# BMS_Sense_Board.net
KiCad netlist of a schematic drawn in Altium Designer
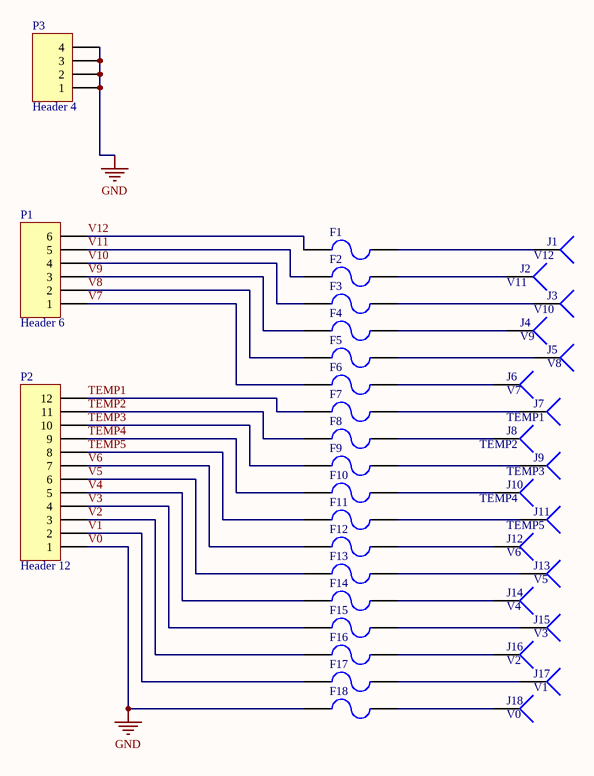
[diagram p0: BMS Sense Board.SchDoc]

(export (version "E")
  (design (tool "Eeschema 10.0.6"))
  (components
    (comp (ref "F1")
      (value "Fuse 2")
      (footprint "6-0805_L")
      (description "Fuse")
      (fields (field (name "PUBLISHER") "Altium Limited"))
      (libsource (lib "Miscellaneous Devices") (part "Fuse 2"))
    )
    (comp (ref "F2")
      (value "Fuse 2")
      (footprint "6-0805_L")
      (description "Fuse")
      (fields (field (name "PUBLISHER") "Altium Limited"))
      (libsource (lib "Miscellaneous Devices") (part "Fuse 2"))
    )
    (comp (ref "F3")
      (value "Fuse 2")
      (footprint "6-0805_L")
      (description "Fuse")
      (fields (field (name "PUBLISHER") "Altium Limited"))
      (libsource (lib "Miscellaneous Devices") (part "Fuse 2"))
    )
    (comp (ref "F4")
      (value "Fuse 2")
      (footprint "6-0805_L")
      (description "Fuse")
      (fields (field (name "PUBLISHER") "Altium Limited"))
      (libsource (lib "Miscellaneous Devices") (part "Fuse 2"))
    )
    (comp (ref "F5")
      (value "Fuse 2")
      (footprint "6-0805_L")
      (description "Fuse")
      (fields (field (name "PUBLISHER") "Altium Limited"))
      (libsource (lib "Miscellaneous Devices") (part "Fuse 2"))
    )
    (comp (ref "F6")
      (value "Fuse 2")
      (footprint "6-0805_L")
      (description "Fuse")
      (fields (field (name "PUBLISHER") "Altium Limited"))
      (libsource (lib "Miscellaneous Devices") (part "Fuse 2"))
    )
    (comp (ref "F7")
      (value "Fuse 2")
      (footprint "6-0805_L")
      (description "Fuse")
      (fields (field (name "PUBLISHER") "Altium Limited"))
      (libsource (lib "Miscellaneous Devices") (part "Fuse 2"))
    )
    (comp (ref "F8")
      (value "Fuse 2")
      (footprint "6-0805_L")
      (description "Fuse")
      (fields (field (name "PUBLISHER") "Altium Limited"))
      (libsource (lib "Miscellaneous Devices") (part "Fuse 2"))
    )
    (comp (ref "F9")
      (value "Fuse 2")
      (footprint "6-0805_L")
      (description "Fuse")
      (fields (field (name "PUBLISHER") "Altium Limited"))
      (libsource (lib "Miscellaneous Devices") (part "Fuse 2"))
    )
    (comp (ref "F10")
      (value "Fuse 2")
      (footprint "6-0805_L")
      (description "Fuse")
      (fields (field (name "PUBLISHER") "Altium Limited"))
      (libsource (lib "Miscellaneous Devices") (part "Fuse 2"))
    )
    (comp (ref "F11")
      (value "Fuse 2")
      (footprint "6-0805_L")
      (description "Fuse")
      (fields (field (name "PUBLISHER") "Altium Limited"))
      (libsource (lib "Miscellaneous Devices") (part "Fuse 2"))
    )
    (comp (ref "F12")
      (value "Fuse 2")
      (footprint "6-0805_L")
      (description "Fuse")
      (fields (field (name "PUBLISHER") "Altium Limited"))
      (libsource (lib "Miscellaneous Devices") (part "Fuse 2"))
    )
    (comp (ref "F13")
      (value "Fuse 2")
      (footprint "6-0805_L")
      (description "Fuse")
      (fields (field (name "PUBLISHER") "Altium Limited"))
      (libsource (lib "Miscellaneous Devices") (part "Fuse 2"))
    )
    (comp (ref "F14")
      (value "Fuse 2")
      (footprint "6-0805_L")
      (description "Fuse")
      (fields (field (name "PUBLISHER") "Altium Limited"))
      (libsource (lib "Miscellaneous Devices") (part "Fuse 2"))
    )
    (comp (ref "F15")
      (value "Fuse 2")
      (footprint "6-0805_L")
      (description "Fuse")
      (fields (field (name "PUBLISHER") "Altium Limited"))
      (libsource (lib "Miscellaneous Devices") (part "Fuse 2"))
    )
    (comp (ref "F16")
      (value "Fuse 2")
      (footprint "6-0805_L")
      (description "Fuse")
      (fields (field (name "PUBLISHER") "Altium Limited"))
      (libsource (lib "Miscellaneous Devices") (part "Fuse 2"))
    )
    (comp (ref "F17")
      (value "Fuse 2")
      (footprint "6-0805_L")
      (description "Fuse")
      (fields (field (name "PUBLISHER") "Altium Limited"))
      (libsource (lib "Miscellaneous Devices") (part "Fuse 2"))
    )
    (comp (ref "F18")
      (value "Fuse 2")
      (footprint "6-0805_L")
      (description "Fuse")
      (fields (field (name "PUBLISHER") "Altium Limited"))
      (libsource (lib "Miscellaneous Devices") (part "Fuse 2"))
    )
    (comp (ref "J1")
      (value "V12")
      (footprint "PAD")
      (description "Socket")
      (fields (field (name "PUBLISHER") "Altium Limited"))
      (libsource (lib "Miscellaneous Connectors") (part "Socket"))
    )
    (comp (ref "J2")
      (value "V11")
      (footprint "PAD")
      (description "Socket")
      (fields (field (name "PUBLISHER") "Altium Limited"))
      (libsource (lib "Miscellaneous Connectors") (part "Socket"))
    )
    (comp (ref "J3")
      (value "V10")
      (footprint "PAD")
      (description "Socket")
      (fields (field (name "PUBLISHER") "Altium Limited"))
      (libsource (lib "Miscellaneous Connectors") (part "Socket"))
    )
    (comp (ref "J4")
      (value "V9")
      (footprint "PAD")
      (description "Socket")
      (fields (field (name "PUBLISHER") "Altium Limited"))
      (libsource (lib "Miscellaneous Connectors") (part "Socket"))
    )
    (comp (ref "J5")
      (value "V8")
      (footprint "PAD")
      (description "Socket")
      (fields (field (name "PUBLISHER") "Altium Limited"))
      (libsource (lib "Miscellaneous Connectors") (part "Socket"))
    )
    (comp (ref "J6")
      (value "V7")
      (footprint "PAD")
      (description "Socket")
      (fields (field (name "PUBLISHER") "Altium Limited"))
      (libsource (lib "Miscellaneous Connectors") (part "Socket"))
    )
    (comp (ref "J7")
      (value "TEMP1")
      (footprint "PAD")
      (description "Socket")
      (fields (field (name "PUBLISHER") "Altium Limited"))
      (libsource (lib "Miscellaneous Connectors") (part "Socket"))
    )
    (comp (ref "J8")
      (value "TEMP2")
      (footprint "PAD")
      (description "Socket")
      (fields (field (name "PUBLISHER") "Altium Limited"))
      (libsource (lib "Miscellaneous Connectors") (part "Socket"))
    )
    (comp (ref "J9")
      (value "TEMP3")
      (footprint "PAD")
      (description "Socket")
      (fields (field (name "PUBLISHER") "Altium Limited"))
      (libsource (lib "Miscellaneous Connectors") (part "Socket"))
    )
    (comp (ref "J10")
      (value "TEMP4")
      (footprint "PAD")
      (description "Socket")
      (fields (field (name "PUBLISHER") "Altium Limited"))
      (libsource (lib "Miscellaneous Connectors") (part "Socket"))
    )
    (comp (ref "J11")
      (value "TEMP5")
      (footprint "PAD")
      (description "Socket")
      (fields (field (name "PUBLISHER") "Altium Limited"))
      (libsource (lib "Miscellaneous Connectors") (part "Socket"))
    )
    (comp (ref "J12")
      (value "V6")
      (footprint "PAD")
      (description "Socket")
      (fields (field (name "PUBLISHER") "Altium Limited"))
      (libsource (lib "Miscellaneous Connectors") (part "Socket"))
    )
    (comp (ref "J13")
      (value "V5")
      (footprint "PAD")
      (description "Socket")
      (fields (field (name "PUBLISHER") "Altium Limited"))
      (libsource (lib "Miscellaneous Connectors") (part "Socket"))
    )
    (comp (ref "J14")
      (value "V4")
      (footprint "PAD")
      (description "Socket")
      (fields (field (name "PUBLISHER") "Altium Limited"))
      (libsource (lib "Miscellaneous Connectors") (part "Socket"))
    )
    (comp (ref "J15")
      (value "V3")
      (footprint "PAD")
      (description "Socket")
      (fields (field (name "PUBLISHER") "Altium Limited"))
      (libsource (lib "Miscellaneous Connectors") (part "Socket"))
    )
    (comp (ref "J16")
      (value "V2")
      (footprint "PAD")
      (description "Socket")
      (fields (field (name "PUBLISHER") "Altium Limited"))
      (libsource (lib "Miscellaneous Connectors") (part "Socket"))
    )
    (comp (ref "J17")
      (value "V1")
      (footprint "PAD")
      (description "Socket")
      (fields (field (name "PUBLISHER") "Altium Limited"))
      (libsource (lib "Miscellaneous Connectors") (part "Socket"))
    )
    (comp (ref "J18")
      (value "V0")
      (footprint "PAD")
      (description "Socket")
      (fields (field (name "PUBLISHER") "Altium Limited"))
      (libsource (lib "Miscellaneous Connectors") (part "Socket"))
    )
    (comp (ref "P1")
      (value "Header 6")
      (footprint "HDR2X3_CEN")
      (description "Header, 6-Pin")
      (fields (field (name "PUBLISHER") "Altium Limited"))
      (libsource (lib "Miscellaneous Connectors") (part "Header 6"))
    )
    (comp (ref "P2")
      (value "Header 12")
      (footprint "HDR2X6")
      (description "Header, 12-Pin")
      (fields (field (name "PUBLISHER") "Altium Limited"))
      (libsource (lib "Miscellaneous Connectors") (part "Header 12"))
    )
    (comp (ref "P3")
      (value "Header 4")
      (footprint "HDR2X2")
      (description "Header, 4-Pin")
      (fields (field (name "PUBLISHER") "Altium Limited"))
      (libsource (lib "Miscellaneous Connectors") (part "Header 4"))
    )
  )
  (nets
    (net (code "1") (name "/TEMP1") (class "Default")
      (node (ref "F7") (pin "1") (pinfunction "1_1") (pintype "passive"))
      (node (ref "P2") (pin "10") (pinfunction "12_10") (pintype "passive"))
    )
    (net (code "2") (name "/TEMP2") (class "Default")
      (node (ref "F8") (pin "1") (pinfunction "1_1") (pintype "passive"))
      (node (ref "P2") (pin "12") (pinfunction "11_12") (pintype "passive"))
    )
    (net (code "3") (name "/TEMP3") (class "Default")
      (node (ref "F9") (pin "1") (pinfunction "1_1") (pintype "passive"))
      (node (ref "P2") (pin "11") (pinfunction "10_11") (pintype "passive"))
    )
    (net (code "4") (name "/TEMP4") (class "Default")
      (node (ref "F10") (pin "1") (pinfunction "1_1") (pintype "passive"))
      (node (ref "P2") (pin "9") (pinfunction "9_9") (pintype "passive"))
    )
    (net (code "5") (name "/TEMP5") (class "Default")
      (node (ref "F11") (pin "1") (pinfunction "1_1") (pintype "passive"))
      (node (ref "P2") (pin "7") (pinfunction "8_7") (pintype "passive"))
    )
    (net (code "6") (name "/V1") (class "Default")
      (node (ref "F17") (pin "1") (pinfunction "1_1") (pintype "passive"))
      (node (ref "P2") (pin "6") (pinfunction "2_6") (pintype "passive"))
    )
    (net (code "7") (name "/V2") (class "Default")
      (node (ref "F16") (pin "1") (pinfunction "1_1") (pintype "passive"))
      (node (ref "P2") (pin "4") (pinfunction "3_4") (pintype "passive"))
    )
    (net (code "8") (name "/V3") (class "Default")
      (node (ref "F15") (pin "1") (pinfunction "1_1") (pintype "passive"))
      (node (ref "P2") (pin "2") (pinfunction "4_2") (pintype "passive"))
    )
    (net (code "9") (name "/V4") (class "Default")
      (node (ref "F14") (pin "1") (pinfunction "1_1") (pintype "passive"))
      (node (ref "P2") (pin "1") (pinfunction "5_1") (pintype "passive"))
    )
    (net (code "10") (name "/V5") (class "Default")
      (node (ref "F13") (pin "1") (pinfunction "1_1") (pintype "passive"))
      (node (ref "P2") (pin "3") (pinfunction "6_3") (pintype "passive"))
    )
    (net (code "11") (name "/V6") (class "Default")
      (node (ref "F12") (pin "1") (pinfunction "1_1") (pintype "passive"))
      (node (ref "P2") (pin "5") (pinfunction "7_5") (pintype "passive"))
    )
    (net (code "12") (name "/V7") (class "Default")
      (node (ref "F6") (pin "1") (pinfunction "1_1") (pintype "passive"))
      (node (ref "P1") (pin "5") (pinfunction "1_5") (pintype "passive"))
    )
    (net (code "13") (name "/V8") (class "Default")
      (node (ref "F5") (pin "1") (pinfunction "1_1") (pintype "passive"))
      (node (ref "P1") (pin "4") (pinfunction "2_4") (pintype "passive"))
    )
    (net (code "14") (name "/V9") (class "Default")
      (node (ref "F4") (pin "1") (pinfunction "1_1") (pintype "passive"))
      (node (ref "P1") (pin "1") (pinfunction "3_1") (pintype "passive"))
    )
    (net (code "15") (name "/V10") (class "Default")
      (node (ref "F3") (pin "1") (pinfunction "1_1") (pintype "passive"))
      (node (ref "P1") (pin "2") (pinfunction "4_2") (pintype "passive"))
    )
    (net (code "16") (name "/V11") (class "Default")
      (node (ref "F2") (pin "1") (pinfunction "1_1") (pintype "passive"))
      (node (ref "P1") (pin "3") (pinfunction "5_3") (pintype "passive"))
    )
    (net (code "17") (name "/V12") (class "Default")
      (node (ref "F1") (pin "1") (pinfunction "1_1") (pintype "passive"))
      (node (ref "P1") (pin "6") (pinfunction "6_6") (pintype "passive"))
    )
    (net (code "18") (name "GND") (class "Default")
      (node (ref "F18") (pin "1") (pinfunction "1_1") (pintype "passive"))
      (node (ref "P2") (pin "8") (pinfunction "1_8") (pintype "passive"))
      (node (ref "P3") (pin "1") (pinfunction "1_1") (pintype "passive"))
      (node (ref "P3") (pin "2") (pinfunction "2_2") (pintype "passive"))
      (node (ref "P3") (pin "3") (pinfunction "3_3") (pintype "passive"))
      (node (ref "P3") (pin "4") (pinfunction "4_4") (pintype "passive"))
    )
    (net (code "19") (name "Net-(F1-Pad2)") (class "Default")
      (node (ref "F1") (pin "2") (pinfunction "2_2") (pintype "passive"))
      (node (ref "J1") (pin "1") (pinfunction "1_1") (pintype "passive"))
    )
    (net (code "20") (name "Net-(F2-Pad2)") (class "Default")
      (node (ref "F2") (pin "2") (pinfunction "2_2") (pintype "passive"))
      (node (ref "J2") (pin "1") (pinfunction "1_1") (pintype "passive"))
    )
    (net (code "21") (name "Net-(F3-Pad2)") (class "Default")
      (node (ref "F3") (pin "2") (pinfunction "2_2") (pintype "passive"))
      (node (ref "J3") (pin "1") (pinfunction "1_1") (pintype "passive"))
    )
    (net (code "22") (name "Net-(F4-Pad2)") (class "Default")
      (node (ref "F4") (pin "2") (pinfunction "2_2") (pintype "passive"))
      (node (ref "J4") (pin "1") (pinfunction "1_1") (pintype "passive"))
    )
    (net (code "23") (name "Net-(F5-Pad2)") (class "Default")
      (node (ref "F5") (pin "2") (pinfunction "2_2") (pintype "passive"))
      (node (ref "J5") (pin "1") (pinfunction "1_1") (pintype "passive"))
    )
    (net (code "24") (name "Net-(F6-Pad2)") (class "Default")
      (node (ref "F6") (pin "2") (pinfunction "2_2") (pintype "passive"))
      (node (ref "J6") (pin "1") (pinfunction "1_1") (pintype "passive"))
    )
    (net (code "25") (name "Net-(F7-Pad2)") (class "Default")
      (node (ref "F7") (pin "2") (pinfunction "2_2") (pintype "passive"))
      (node (ref "J7") (pin "1") (pinfunction "1_1") (pintype "passive"))
    )
    (net (code "26") (name "Net-(F8-Pad2)") (class "Default")
      (node (ref "F8") (pin "2") (pinfunction "2_2") (pintype "passive"))
      (node (ref "J8") (pin "1") (pinfunction "1_1") (pintype "passive"))
    )
    (net (code "27") (name "Net-(F9-Pad2)") (class "Default")
      (node (ref "F9") (pin "2") (pinfunction "2_2") (pintype "passive"))
      (node (ref "J9") (pin "1") (pinfunction "1_1") (pintype "passive"))
    )
    (net (code "28") (name "Net-(F10-Pad2)") (class "Default")
      (node (ref "F10") (pin "2") (pinfunction "2_2") (pintype "passive"))
      (node (ref "J10") (pin "1") (pinfunction "1_1") (pintype "passive"))
    )
    (net (code "29") (name "Net-(F11-Pad2)") (class "Default")
      (node (ref "F11") (pin "2") (pinfunction "2_2") (pintype "passive"))
      (node (ref "J11") (pin "1") (pinfunction "1_1") (pintype "passive"))
    )
    (net (code "30") (name "Net-(F12-Pad2)") (class "Default")
      (node (ref "F12") (pin "2") (pinfunction "2_2") (pintype "passive"))
      (node (ref "J12") (pin "1") (pinfunction "1_1") (pintype "passive"))
    )
    (net (code "31") (name "Net-(F13-Pad2)") (class "Default")
      (node (ref "F13") (pin "2") (pinfunction "2_2") (pintype "passive"))
      (node (ref "J13") (pin "1") (pinfunction "1_1") (pintype "passive"))
    )
    (net (code "32") (name "Net-(F14-Pad2)") (class "Default")
      (node (ref "F14") (pin "2") (pinfunction "2_2") (pintype "passive"))
      (node (ref "J14") (pin "1") (pinfunction "1_1") (pintype "passive"))
    )
    (net (code "33") (name "Net-(F15-Pad2)") (class "Default")
      (node (ref "F15") (pin "2") (pinfunction "2_2") (pintype "passive"))
      (node (ref "J15") (pin "1") (pinfunction "1_1") (pintype "passive"))
    )
    (net (code "34") (name "Net-(F16-Pad2)") (class "Default")
      (node (ref "F16") (pin "2") (pinfunction "2_2") (pintype "passive"))
      (node (ref "J16") (pin "1") (pinfunction "1_1") (pintype "passive"))
    )
    (net (code "35") (name "Net-(F17-Pad2)") (class "Default")
      (node (ref "F17") (pin "2") (pinfunction "2_2") (pintype "passive"))
      (node (ref "J17") (pin "1") (pinfunction "1_1") (pintype "passive"))
    )
    (net (code "36") (name "Net-(F18-Pad2)") (class "Default")
      (node (ref "F18") (pin "2") (pinfunction "2_2") (pintype "passive"))
      (node (ref "J18") (pin "1") (pinfunction "1_1") (pintype "passive"))
    )
  )
)
